# MotorControllerV_Driver1_1.net
KiCad netlist of a schematic drawn in Altium Designer
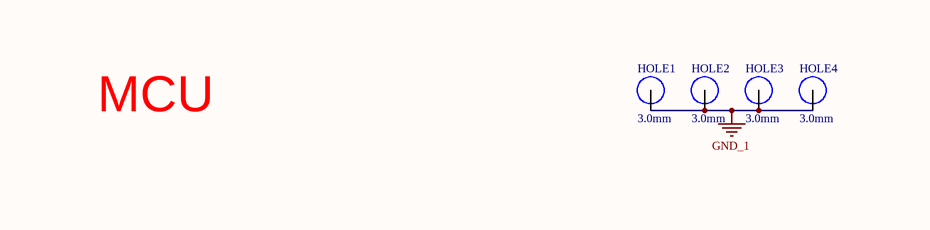
[diagram p0: MotorControllerV_Driver1.1.SchDoc, top left]
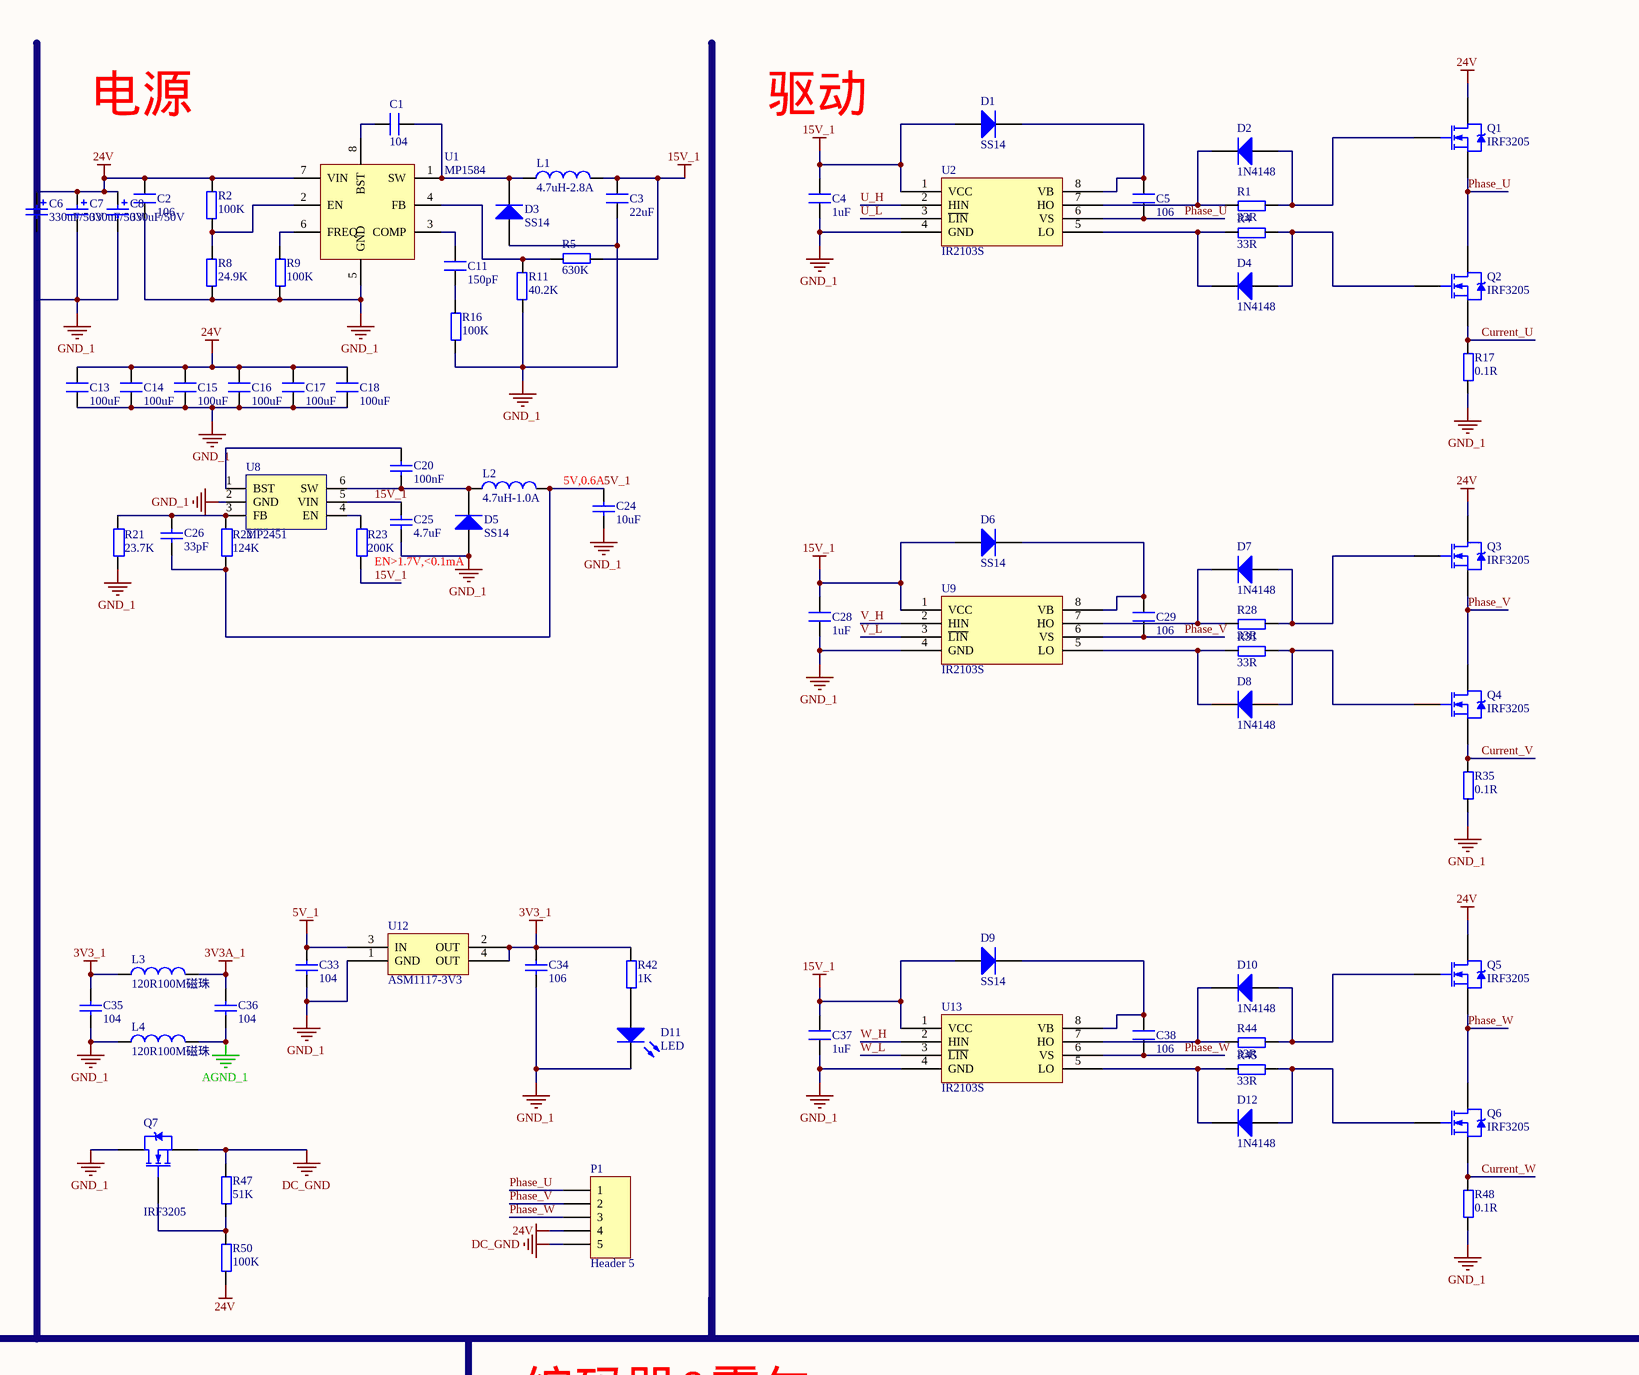
[diagram p1: MotorControllerV_Driver1.1.SchDoc, top middle]
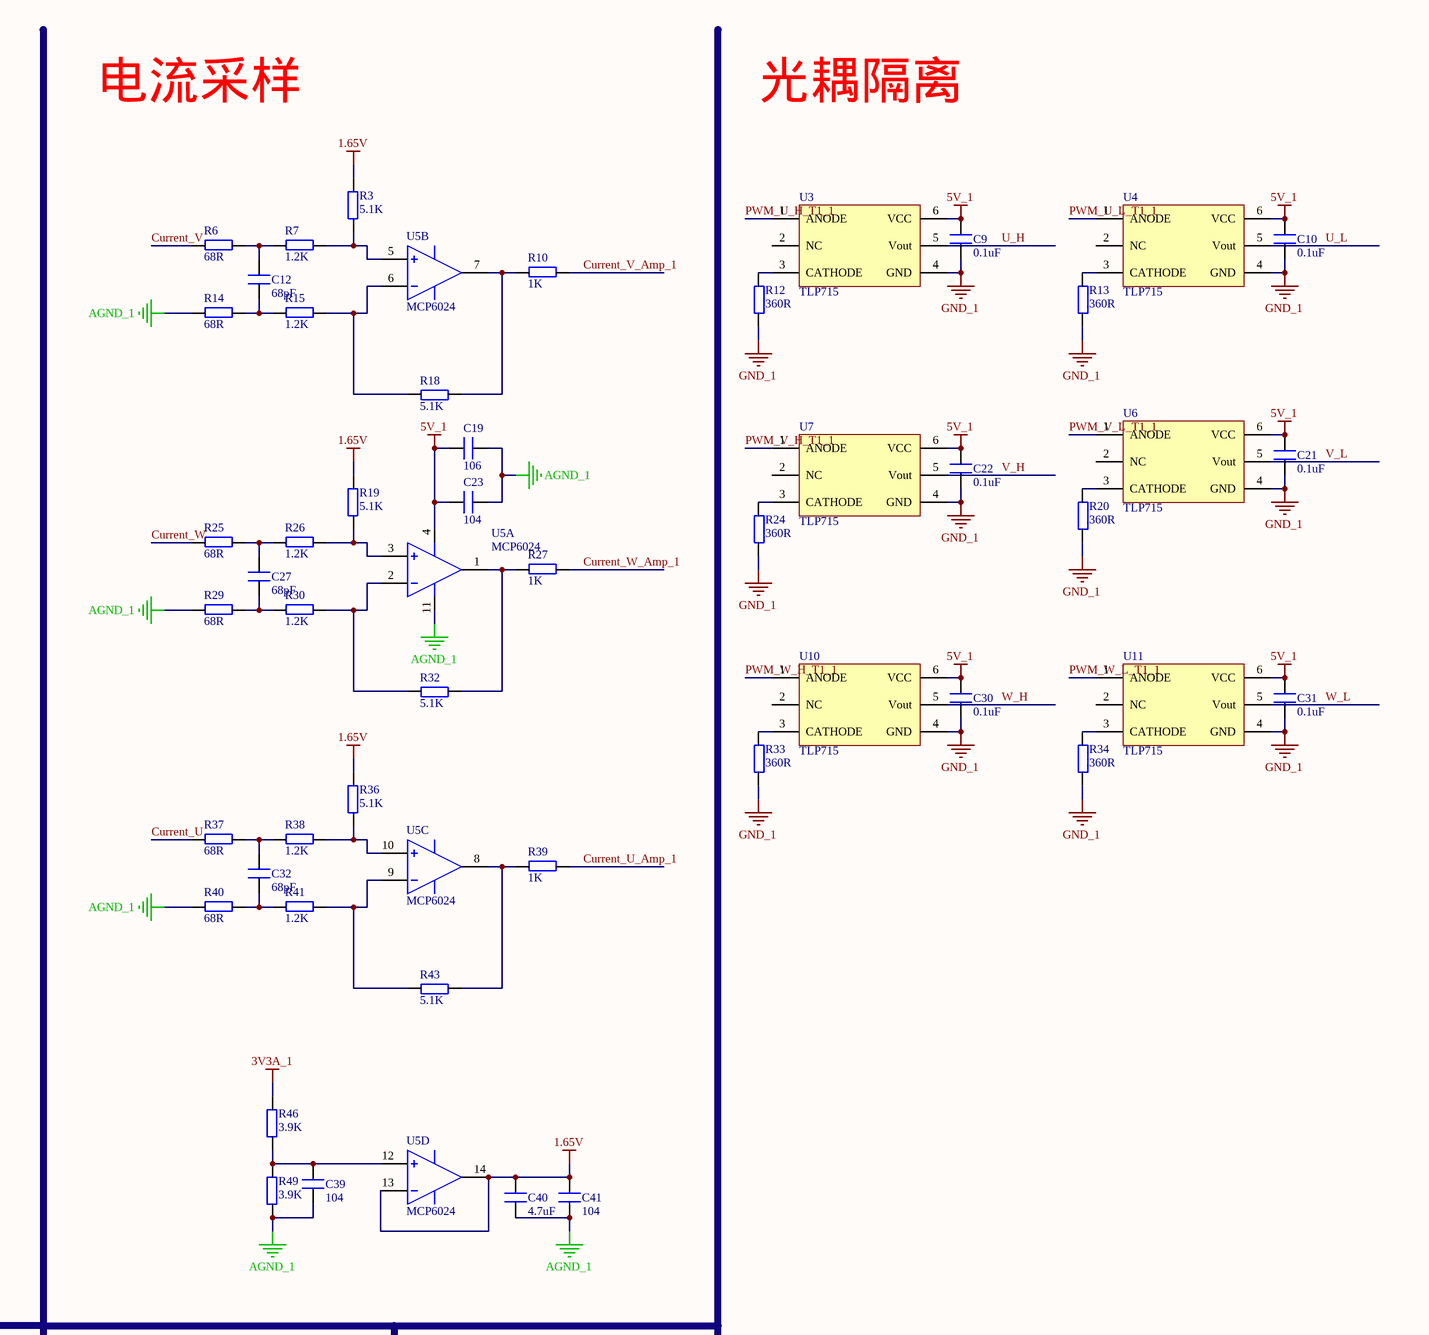
[diagram p2: MotorControllerV_Driver1.1.SchDoc, top right]
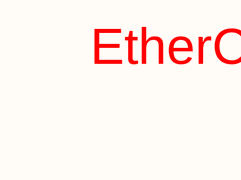
[diagram p3: MotorControllerV_Driver1.1.SchDoc, bottom left]
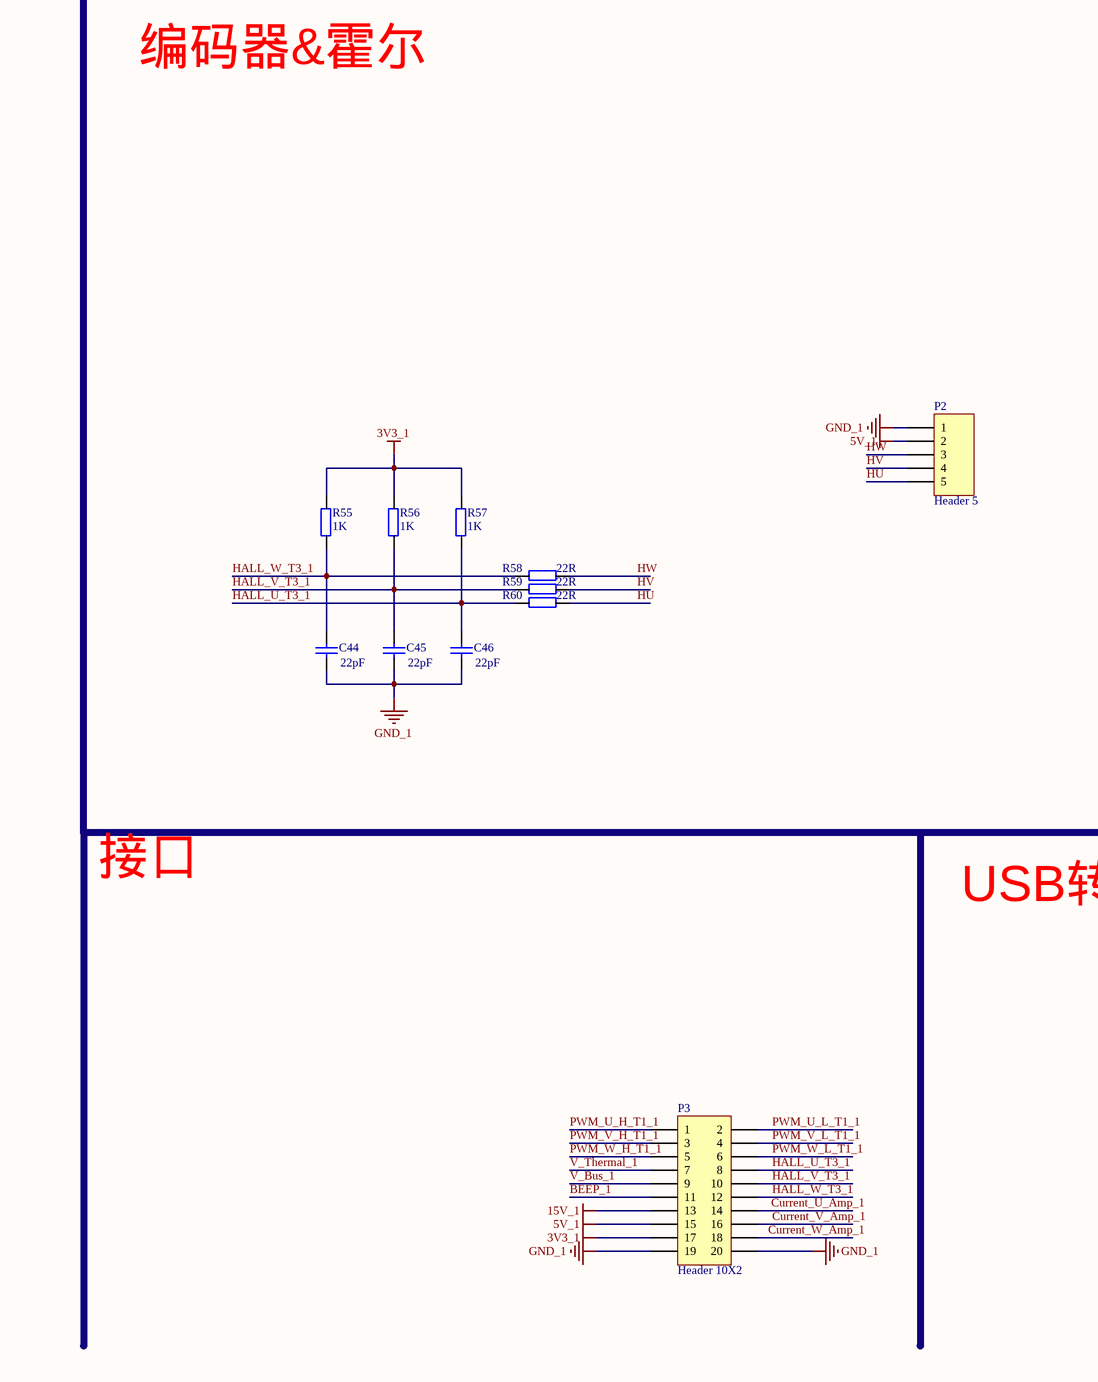
[diagram p4: MotorControllerV_Driver1.1.SchDoc, bottom middle]
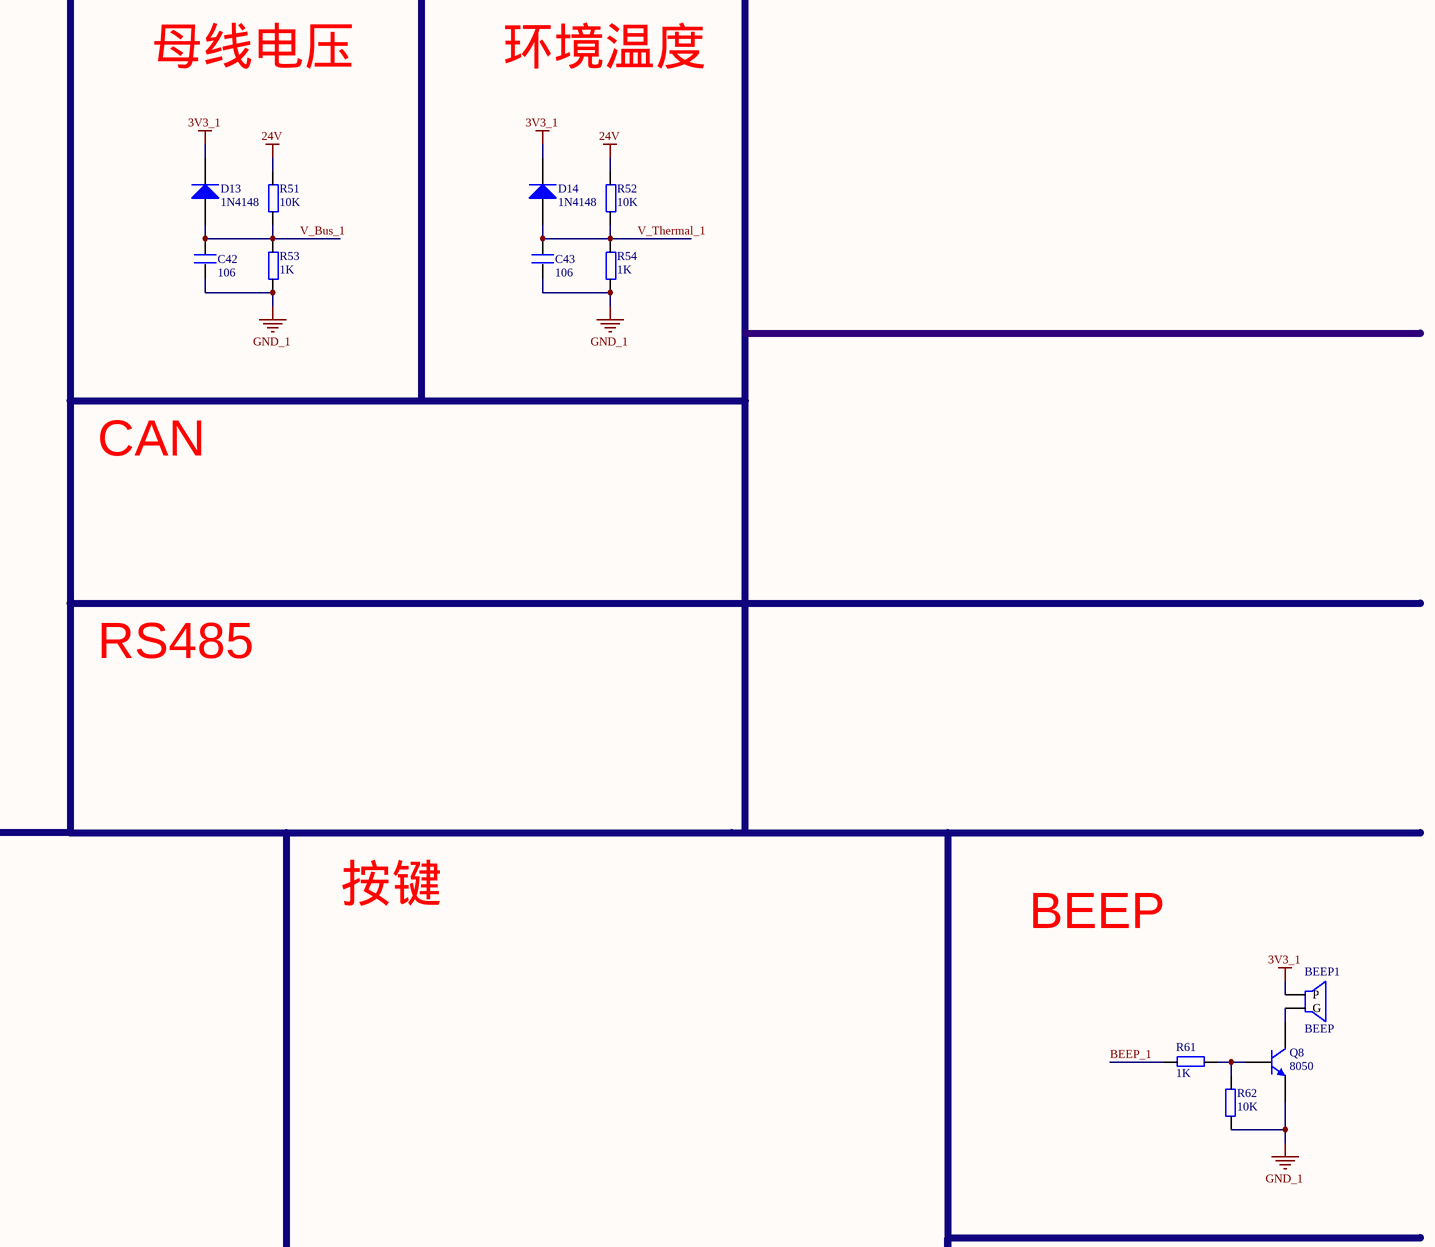
[diagram p5: MotorControllerV_Driver1.1.SchDoc, bottom right]

(export (version "E")
  (design (tool "Eeschema 10.0.6"))
  (components
    (comp (ref "BEEP1") (value "BEEP") (footprint "BEEP 5x9x5.5") (libsource (lib "MYSchlib") (part "BEEP")))
    (comp (ref "C1") (value "104") (footprint "0603_C") (libsource (lib "MYSchlib") (part "C")))
    (comp (ref "C2") (value "106") (footprint "0603_C") (libsource (lib "MYSchlib") (part "C")))
    (comp (ref "C3") (value "22uF") (footprint "0603_C") (libsource (lib "MYSchlib") (part "C")))
    (comp (ref "C4") (value "1uF") (footprint "0603_C") (libsource (lib "MYSchlib") (part "C")))
    (comp (ref "C5") (value "106") (footprint "1210_C") (libsource (lib "MYSchlib") (part "C")))
    (comp (ref "C6")
      (value "330uF/50V")
      (footprint "CM F(10*10.2)")
      (description "C+")
      (fields (field (name "PUBLISHER") "Altium Limited"))
      (libsource (lib "RLC") (part "C+"))
    )
    (comp (ref "C7")
      (value "330uF/50V")
      (footprint "CM F(10*10.2)")
      (description "C+")
      (fields (field (name "PUBLISHER") "Altium Limited"))
      (libsource (lib "RLC") (part "C+"))
    )
    (comp (ref "C8")
      (value "330uF/50V")
      (footprint "CM F(10*10.2)")
      (description "C+")
      (fields (field (name "PUBLISHER") "Altium Limited"))
      (libsource (lib "RLC") (part "C+"))
    )
    (comp (ref "C9") (value "0.1uF") (footprint "0603_C") (libsource (lib "MYSchlib") (part "C")))
    (comp (ref "C10") (value "0.1uF") (footprint "0603_C") (libsource (lib "MYSchlib") (part "C")))
    (comp (ref "C11") (value "150pF") (footprint "0603_C") (libsource (lib "MYSchlib") (part "C")))
    (comp (ref "C12") (value "68pF") (footprint "0603_C") (libsource (lib "MYSchlib") (part "C")))
    (comp (ref "C13") (value "100uF") (footprint "1210_C") (libsource (lib "MYSchlib") (part "C")))
    (comp (ref "C14") (value "100uF") (footprint "1210_C") (libsource (lib "MYSchlib") (part "C")))
    (comp (ref "C15") (value "100uF") (footprint "1210_C") (libsource (lib "MYSchlib") (part "C")))
    (comp (ref "C16") (value "100uF") (footprint "1210_C") (libsource (lib "MYSchlib") (part "C")))
    (comp (ref "C17") (value "100uF") (footprint "1210_C") (libsource (lib "MYSchlib") (part "C")))
    (comp (ref "C18") (value "100uF") (footprint "1210_C") (libsource (lib "MYSchlib") (part "C")))
    (comp (ref "C19") (value "106") (footprint "0603_C") (libsource (lib "MYSchlib") (part "C")))
    (comp (ref "C20")
      (value "100nF")
      (footprint "0603_C")
      (description "C")
      (fields (field (name "PUBLISHER") "Altium Limited"))
      (libsource (lib "RLC") (part "C"))
    )
    (comp (ref "C21") (value "0.1uF") (footprint "0603_C") (libsource (lib "MYSchlib") (part "C")))
    (comp (ref "C22") (value "0.1uF") (footprint "0603_C") (libsource (lib "MYSchlib") (part "C")))
    (comp (ref "C23") (value "104") (footprint "0603_C") (libsource (lib "MYSchlib") (part "C")))
    (comp (ref "C24")
      (value "10uF")
      (footprint "0603_C")
      (description "C")
      (fields (field (name "PUBLISHER") "Altium Limited"))
      (libsource (lib "RLC") (part "C"))
    )
    (comp (ref "C25")
      (value "4.7uF")
      (footprint "0603_C")
      (description "C")
      (fields (field (name "PUBLISHER") "Altium Limited"))
      (libsource (lib "RLC") (part "C"))
    )
    (comp (ref "C26")
      (value "33pF")
      (footprint "0603_C")
      (description "C")
      (fields (field (name "PUBLISHER") "Altium Limited"))
      (libsource (lib "RLC") (part "C"))
    )
    (comp (ref "C27") (value "68pF") (footprint "0603_C") (libsource (lib "MYSchlib") (part "C")))
    (comp (ref "C28") (value "1uF") (footprint "0603_C") (libsource (lib "MYSchlib") (part "C")))
    (comp (ref "C29") (value "106") (footprint "1210_C") (libsource (lib "MYSchlib") (part "C")))
    (comp (ref "C30") (value "0.1uF") (footprint "0603_C") (libsource (lib "MYSchlib") (part "C")))
    (comp (ref "C31") (value "0.1uF") (footprint "0603_C") (libsource (lib "MYSchlib") (part "C")))
    (comp (ref "C32") (value "68pF") (footprint "0603_C") (libsource (lib "MYSchlib") (part "C")))
    (comp (ref "C33")
      (value "104")
      (footprint "0603_C")
      (description "C")
      (fields (field (name "PUBLISHER") "Altium Limited"))
      (libsource (lib "RLC") (part "C"))
    )
    (comp (ref "C34")
      (value "106")
      (footprint "0603_C")
      (description "C")
      (fields (field (name "PUBLISHER") "Altium Limited"))
      (libsource (lib "RLC") (part "C"))
    )
    (comp (ref "C35")
      (value "104")
      (footprint "0603_C")
      (description "C")
      (fields (field (name "PUBLISHER") "Altium Limited"))
      (libsource (lib "RLC") (part "C"))
    )
    (comp (ref "C36")
      (value "104")
      (footprint "0603_C")
      (description "C")
      (fields (field (name "PUBLISHER") "Altium Limited"))
      (libsource (lib "RLC") (part "C"))
    )
    (comp (ref "C37") (value "1uF") (footprint "0603_C") (libsource (lib "MYSchlib") (part "C")))
    (comp (ref "C38") (value "106") (footprint "1210_C") (libsource (lib "MYSchlib") (part "C")))
    (comp (ref "C39") (value "104") (footprint "0603_C") (libsource (lib "MYSchlib") (part "C")))
    (comp (ref "C40") (value "4.7uF") (footprint "0603_C") (libsource (lib "MYSchlib") (part "C")))
    (comp (ref "C41") (value "104") (footprint "0603_C") (libsource (lib "MYSchlib") (part "C")))
    (comp (ref "C42") (value "106") (footprint "0603_C") (libsource (lib "MYSchlib") (part "C")))
    (comp (ref "C43") (value "106") (footprint "0603_C") (libsource (lib "MYSchlib") (part "C")))
    (comp (ref "C44")
      (value "22pF")
      (footprint "0603_C")
      (description "Capacitor")
      (fields (field (name "PUBLISHER") "Altium Limited"))
      (libsource (lib "Miscellaneous Devices") (part "Cap"))
    )
    (comp (ref "C45")
      (value "22pF")
      (footprint "0603_C")
      (description "Capacitor")
      (fields (field (name "PUBLISHER") "Altium Limited"))
      (libsource (lib "Miscellaneous Devices") (part "Cap"))
    )
    (comp (ref "C46")
      (value "22pF")
      (footprint "0603_C")
      (description "Capacitor")
      (fields (field (name "PUBLISHER") "Altium Limited"))
      (libsource (lib "Miscellaneous Devices") (part "Cap"))
    )
    (comp (ref "D1")
      (value "SS14")
      (footprint "二极管-整流桥:SOD-323")
      (description "D")
      (libsource (lib "MYSchlib") (part "Dio"))
    )
    (comp (ref "D2")
      (value "1N4148")
      (footprint "SOD-123F")
      (description "D")
      (libsource (lib "MYSchlib") (part "Dio"))
    )
    (comp (ref "D3")
      (value "SS14")
      (footprint "二极管-整流桥:SMA")
      (description "D")
      (libsource (lib "MYSchlib") (part "Dio"))
    )
    (comp (ref "D4")
      (value "1N4148")
      (footprint "SOD-123F")
      (description "D")
      (libsource (lib "MYSchlib") (part "Dio"))
    )
    (comp (ref "D5")
      (value "SS14")
      (footprint "二极管-整流桥:SOD-323")
      (description "D")
      (libsource (lib "MYSchlib") (part "Dio"))
    )
    (comp (ref "D6")
      (value "SS14")
      (footprint "二极管-整流桥:SOD-323")
      (description "D")
      (libsource (lib "MYSchlib") (part "Dio"))
    )
    (comp (ref "D7")
      (value "1N4148")
      (footprint "SOD-123F")
      (description "D")
      (libsource (lib "MYSchlib") (part "Dio"))
    )
    (comp (ref "D8")
      (value "1N4148")
      (footprint "SOD-123F")
      (description "D")
      (libsource (lib "MYSchlib") (part "Dio"))
    )
    (comp (ref "D9")
      (value "SS14")
      (footprint "二极管-整流桥:SOD-323")
      (description "D")
      (libsource (lib "MYSchlib") (part "Dio"))
    )
    (comp (ref "D10")
      (value "1N4148")
      (footprint "SOD-123F")
      (description "D")
      (libsource (lib "MYSchlib") (part "Dio"))
    )
    (comp (ref "D11") (value "LED") (footprint "0603_LED") (libsource (lib "MYSchlib") (part "LED")))
    (comp (ref "D12")
      (value "1N4148")
      (footprint "SOD-123F")
      (description "D")
      (libsource (lib "MYSchlib") (part "Dio"))
    )
    (comp (ref "D13")
      (value "1N4148")
      (footprint "SOD-123F")
      (description "D")
      (libsource (lib "MYSchlib") (part "Dio"))
    )
    (comp (ref "D14")
      (value "1N4148")
      (footprint "SOD-123F")
      (description "D")
      (libsource (lib "MYSchlib") (part "Dio"))
    )
    (comp (ref "HOLE1")
      (value "3.0mm")
      (footprint "M2.5x6+6_L")
      (fields (field (name "Comment") "HOLE"))
      (libsource (lib "MYSchlib") (part "HOLE"))
    )
    (comp (ref "HOLE2")
      (value "3.0mm")
      (footprint "M2.5x6+6_L")
      (fields (field (name "Comment") "HOLE"))
      (libsource (lib "MYSchlib") (part "HOLE"))
    )
    (comp (ref "HOLE3")
      (value "3.0mm")
      (footprint "M2.5x6+6_L")
      (fields (field (name "Comment") "HOLE"))
      (libsource (lib "MYSchlib") (part "HOLE"))
    )
    (comp (ref "HOLE4")
      (value "3.0mm")
      (footprint "M2.5x6+6_L")
      (fields (field (name "Comment") "HOLE"))
      (libsource (lib "MYSchlib") (part "HOLE"))
    )
    (comp (ref "L1")
      (value "4.7uH-2.8A")
      (footprint "CDRH74")
      (description "L")
      (fields (field (name "PUBLISHER") "Altium Limited"))
      (libsource (lib "RLC") (part "L"))
    )
    (comp (ref "L2")
      (value "4.7uH-1.0A")
      (footprint "CD32")
      (description "L")
      (fields (field (name "PUBLISHER") "Altium Limited"))
      (libsource (lib "RLC") (part "L"))
    )
    (comp (ref "L3")
      (value "120R100M磁珠")
      (footprint "0603_R")
      (description "L")
      (fields (field (name "PUBLISHER") "Altium Limited"))
      (libsource (lib "MYSchlib") (part "L_1"))
    )
    (comp (ref "L4")
      (value "120R100M磁珠")
      (footprint "0603_R")
      (description "L")
      (fields (field (name "PUBLISHER") "Altium Limited"))
      (libsource (lib "MYSchlib") (part "L_1"))
    )
    (comp (ref "P1")
      (value "Header 5")
      (footprint "HT5.08-5P")
      (description "Header, 5-Pin")
      (fields (field (name "PUBLISHER") "Altium Limited"))
      (libsource (lib "MYSchlib") (part "Header 5"))
    )
    (comp (ref "P2")
      (value "Header 5")
      (footprint "HDR2.54-WI-5P")
      (description "Header, 5-Pin")
      (fields (field (name "PUBLISHER") "Altium Limited"))
      (libsource (lib "Miscellaneous Connectors") (part "Header 5"))
    )
    (comp (ref "P3")
      (value "Header 10X2")
      (footprint "MYPcbLib:HDR2.54-LI-2x10P")
      (description "Header, 10-Pin, Dual row")
      (fields (field (name "PUBLISHER") "Altium Limited"))
      (libsource (lib "Miscellaneous Connectors") (part "Header 10X2"))
    )
    (comp (ref "Q1")
      (value "IRF3205")
      (footprint "TO252")
      (description "N-Channel Power MOSFET")
      (fields (field (name "PUBLISHER") "Altium Limited"))
      (libsource (lib "MYSchlib") (part "NMOS-2"))
    )
    (comp (ref "Q2")
      (value "IRF3205")
      (footprint "TO252")
      (description "N-Channel Power MOSFET")
      (fields (field (name "PUBLISHER") "Altium Limited"))
      (libsource (lib "MYSchlib") (part "NMOS-2"))
    )
    (comp (ref "Q3")
      (value "IRF3205")
      (footprint "TO252")
      (description "N-Channel Power MOSFET")
      (fields (field (name "PUBLISHER") "Altium Limited"))
      (libsource (lib "MYSchlib") (part "NMOS-2"))
    )
    (comp (ref "Q4")
      (value "IRF3205")
      (footprint "TO252")
      (description "N-Channel Power MOSFET")
      (fields (field (name "PUBLISHER") "Altium Limited"))
      (libsource (lib "MYSchlib") (part "NMOS-2"))
    )
    (comp (ref "Q5")
      (value "IRF3205")
      (footprint "TO252")
      (description "N-Channel Power MOSFET")
      (fields (field (name "PUBLISHER") "Altium Limited"))
      (libsource (lib "MYSchlib") (part "NMOS-2"))
    )
    (comp (ref "Q6")
      (value "IRF3205")
      (footprint "TO252")
      (description "N-Channel Power MOSFET")
      (fields (field (name "PUBLISHER") "Altium Limited"))
      (libsource (lib "MYSchlib") (part "NMOS-2"))
    )
    (comp (ref "Q7")
      (value "IRF3205")
      (footprint "TO252")
      (description "N-Channel Power MOSFET")
      (fields (field (name "PUBLISHER") "Altium Limited"))
      (libsource (lib "MYSchlib") (part "NMOS-2"))
    )
    (comp (ref "Q8")
      (value "8050")
      (footprint "SOT23")
      (description "NPN Bipolar Transistor")
      (fields (field (name "PUBLISHER") "Altium Limited"))
      (libsource (lib "MYSchlib") (part "NPN_1"))
    )
    (comp (ref "R1") (value "33R") (footprint "0603_R") (libsource (lib "MYSchlib") (part "R")))
    (comp (ref "R2") (value "100K") (footprint "0603_R") (libsource (lib "MYSchlib") (part "R")))
    (comp (ref "R3") (value "5.1K") (footprint "0603_R") (libsource (lib "MYSchlib") (part "R")))
    (comp (ref "R4") (value "33R") (footprint "0603_R") (libsource (lib "MYSchlib") (part "R")))
    (comp (ref "R5") (value "630K") (footprint "0603_R") (libsource (lib "MYSchlib") (part "R")))
    (comp (ref "R6") (value "68R") (footprint "0603_R") (libsource (lib "MYSchlib") (part "R")))
    (comp (ref "R7") (value "1.2K") (footprint "0603_R") (libsource (lib "MYSchlib") (part "R")))
    (comp (ref "R8") (value "24.9K") (footprint "0603_R") (libsource (lib "MYSchlib") (part "R")))
    (comp (ref "R9") (value "100K") (footprint "0603_R") (libsource (lib "MYSchlib") (part "R")))
    (comp (ref "R10") (value "1K") (footprint "0603_R") (libsource (lib "MYSchlib") (part "R")))
    (comp (ref "R11") (value "40.2K") (footprint "0603_R") (libsource (lib "MYSchlib") (part "R")))
    (comp (ref "R12") (value "360R") (footprint "0603_R") (libsource (lib "MYSchlib") (part "R")))
    (comp (ref "R13") (value "360R") (footprint "0603_R") (libsource (lib "MYSchlib") (part "R")))
    (comp (ref "R14") (value "68R") (footprint "0603_R") (libsource (lib "MYSchlib") (part "R")))
    (comp (ref "R15") (value "1.2K") (footprint "0603_R") (libsource (lib "MYSchlib") (part "R")))
    (comp (ref "R16") (value "100K") (footprint "0603_R") (libsource (lib "MYSchlib") (part "R")))
    (comp (ref "R17") (value "0.1R") (footprint "R_2512") (libsource (lib "MYSchlib") (part "R")))
    (comp (ref "R18") (value "5.1K") (footprint "0603_R") (libsource (lib "MYSchlib") (part "R")))
    (comp (ref "R19") (value "5.1K") (footprint "0603_R") (libsource (lib "MYSchlib") (part "R")))
    (comp (ref "R20") (value "360R") (footprint "0603_R") (libsource (lib "MYSchlib") (part "R")))
    (comp (ref "R21")
      (value "23.7K")
      (footprint "0603_R")
      (description "R")
      (fields (field (name "PUBLISHER") "Altium Limited"))
      (libsource (lib "RLC") (part "R"))
    )
    (comp (ref "R22")
      (value "124K")
      (footprint "0603_R")
      (description "R")
      (fields (field (name "PUBLISHER") "Altium Limited"))
      (libsource (lib "RLC") (part "R"))
    )
    (comp (ref "R23")
      (value "200K")
      (footprint "0603_R")
      (description "R")
      (fields (field (name "PUBLISHER") "Altium Limited"))
      (libsource (lib "RLC") (part "R"))
    )
    (comp (ref "R24") (value "360R") (footprint "0603_R") (libsource (lib "MYSchlib") (part "R")))
    (comp (ref "R25") (value "68R") (footprint "0603_R") (libsource (lib "MYSchlib") (part "R")))
    (comp (ref "R26") (value "1.2K") (footprint "0603_R") (libsource (lib "MYSchlib") (part "R")))
    (comp (ref "R27") (value "1K") (footprint "0603_R") (libsource (lib "MYSchlib") (part "R")))
    (comp (ref "R28") (value "33R") (footprint "0603_R") (libsource (lib "MYSchlib") (part "R")))
    (comp (ref "R29") (value "68R") (footprint "0603_R") (libsource (lib "MYSchlib") (part "R")))
    (comp (ref "R30") (value "1.2K") (footprint "0603_R") (libsource (lib "MYSchlib") (part "R")))
    (comp (ref "R31") (value "33R") (footprint "0603_R") (libsource (lib "MYSchlib") (part "R")))
    (comp (ref "R32") (value "5.1K") (footprint "0603_R") (libsource (lib "MYSchlib") (part "R")))
    (comp (ref "R33") (value "360R") (footprint "0603_R") (libsource (lib "MYSchlib") (part "R")))
    (comp (ref "R34") (value "360R") (footprint "0603_R") (libsource (lib "MYSchlib") (part "R")))
    (comp (ref "R35") (value "0.1R") (footprint "R_2512") (libsource (lib "MYSchlib") (part "R")))
    (comp (ref "R36") (value "5.1K") (footprint "0603_R") (libsource (lib "MYSchlib") (part "R")))
    (comp (ref "R37") (value "68R") (footprint "0603_R") (libsource (lib "MYSchlib") (part "R")))
    (comp (ref "R38") (value "1.2K") (footprint "0603_R") (libsource (lib "MYSchlib") (part "R")))
    (comp (ref "R39") (value "1K") (footprint "0603_R") (libsource (lib "MYSchlib") (part "R")))
    (comp (ref "R40") (value "68R") (footprint "0603_R") (libsource (lib "MYSchlib") (part "R")))
    (comp (ref "R41") (value "1.2K") (footprint "0603_R") (libsource (lib "MYSchlib") (part "R")))
    (comp (ref "R42") (value "1K") (footprint "0603_R") (libsource (lib "MYSchlib") (part "R")))
    (comp (ref "R43") (value "5.1K") (footprint "0603_R") (libsource (lib "MYSchlib") (part "R")))
    (comp (ref "R44") (value "33R") (footprint "0603_R") (libsource (lib "MYSchlib") (part "R")))
    (comp (ref "R45") (value "33R") (footprint "0603_R") (libsource (lib "MYSchlib") (part "R")))
    (comp (ref "R46") (value "3.9K") (footprint "0603_R") (libsource (lib "MYSchlib") (part "R")))
    (comp (ref "R47") (value "51K") (footprint "0603_R") (libsource (lib "MYSchlib") (part "R")))
    (comp (ref "R48") (value "0.1R") (footprint "R_2512") (libsource (lib "MYSchlib") (part "R")))
    (comp (ref "R49") (value "3.9K") (footprint "0603_R") (libsource (lib "MYSchlib") (part "R")))
    (comp (ref "R50") (value "100K") (footprint "0603_R") (libsource (lib "MYSchlib") (part "R")))
    (comp (ref "R51") (value "10K") (footprint "0603_R") (libsource (lib "MYSchlib") (part "R")))
    (comp (ref "R52") (value "10K") (footprint "Thermistor_MF52") (libsource (lib "MYSchlib") (part "R")))
    (comp (ref "R53") (value "1K") (footprint "0603_R") (libsource (lib "MYSchlib") (part "R")))
    (comp (ref "R54") (value "1K") (footprint "0603_R") (libsource (lib "MYSchlib") (part "R")))
    (comp (ref "R55") (value "1K") (footprint "0603_R") (libsource (lib "MYSchlib") (part "R")))
    (comp (ref "R56") (value "1K") (footprint "0603_R") (libsource (lib "MYSchlib") (part "R")))
    (comp (ref "R57") (value "1K") (footprint "0603_R") (libsource (lib "MYSchlib") (part "R")))
    (comp (ref "R58") (value "22R") (footprint "0603_R") (libsource (lib "MYSchlib") (part "R")))
    (comp (ref "R59") (value "22R") (footprint "0603_R") (libsource (lib "MYSchlib") (part "R")))
    (comp (ref "R60") (value "22R") (footprint "0603_R") (libsource (lib "MYSchlib") (part "R")))
    (comp (ref "R61") (value "1K") (footprint "0603_R") (libsource (lib "MYSchlib") (part "R")))
    (comp (ref "R62") (value "10K") (footprint "0603_R") (libsource (lib "MYSchlib") (part "R")))
    (comp (ref "U1")
      (value "MP1584")
      (footprint "MYPcbLib:SOIC-8E")
      (libsource (lib "MYSchlib") (part "MP1584"))
    )
    (comp (ref "U2") (value "IR2103S") (footprint "SOP-8") (libsource (lib "MYSchlib") (part "IR2103S")))
    (comp (ref "U3") (value "TLP715") (footprint "SOP-6") (libsource (lib "MYSchlib") (part "TLP715")))
    (comp (ref "U4") (value "TLP715") (footprint "SOP-6") (libsource (lib "MYSchlib") (part "TLP715")))
    (comp (ref "U5")
      (value "MCP6024")
      (footprint "SOIC-14_150mil")
      (libsource (lib "MYSchlib") (part "MCP6024"))
    )
    (comp (ref "U6") (value "TLP715") (footprint "SOP-6") (libsource (lib "MYSchlib") (part "TLP715")))
    (comp (ref "U7") (value "TLP715") (footprint "SOP-6") (libsource (lib "MYSchlib") (part "TLP715")))
    (comp (ref "U8") (value "MP2451") (footprint "SOT23-6") (libsource (lib "MYSchlib") (part "MP2451")))
    (comp (ref "U9") (value "IR2103S") (footprint "SOP-8") (libsource (lib "MYSchlib") (part "IR2103S")))
    (comp (ref "U10") (value "TLP715") (footprint "SOP-6") (libsource (lib "MYSchlib") (part "TLP715")))
    (comp (ref "U11") (value "TLP715") (footprint "SOP-6") (libsource (lib "MYSchlib") (part "TLP715")))
    (comp (ref "U12")
      (value "ASM1117-3V3")
      (footprint "SOT-223")
      (description "3.3V稳压芯片")
      (libsource (lib "MYSchlib") (part "ASM1117"))
    )
    (comp (ref "U13") (value "IR2103S") (footprint "SOP-8") (libsource (lib "MYSchlib") (part "IR2103S")))
  )
  (nets
    (net (code "1") (name "/BEEP_1") (class "Default")
      (node (ref "P3") (pin "11") (pinfunction "11_11") (pintype "passive"))
      (node (ref "R61") (pin "2") (pintype "passive"))
    )
    (net (code "2") (name "/Current_U") (class "Default")
      (node (ref "Q2") (pin "3") (pinfunction "S_3") (pintype "passive"))
      (node (ref "R17") (pin "2") (pintype "passive"))
      (node (ref "R37") (pin "2") (pintype "passive"))
    )
    (net (code "3") (name "/Current_U_Amp_1") (class "Default")
      (node (ref "P3") (pin "14") (pinfunction "14_14") (pintype "passive"))
      (node (ref "R39") (pin "1") (pintype "passive"))
    )
    (net (code "4") (name "/Current_V") (class "Default")
      (node (ref "Q4") (pin "3") (pinfunction "S_3") (pintype "passive"))
      (node (ref "R35") (pin "2") (pintype "passive"))
      (node (ref "R6") (pin "2") (pintype "passive"))
    )
    (net (code "5") (name "/Current_V_Amp_1") (class "Default")
      (node (ref "P3") (pin "16") (pinfunction "16_16") (pintype "passive"))
      (node (ref "R10") (pin "1") (pintype "passive"))
    )
    (net (code "6") (name "/Current_W") (class "Default")
      (node (ref "Q6") (pin "3") (pinfunction "S_3") (pintype "passive"))
      (node (ref "R25") (pin "2") (pintype "passive"))
      (node (ref "R48") (pin "2") (pintype "passive"))
    )
    (net (code "7") (name "/Current_W_Amp_1") (class "Default")
      (node (ref "P3") (pin "18") (pinfunction "18_18") (pintype "passive"))
      (node (ref "R27") (pin "1") (pintype "passive"))
    )
    (net (code "8") (name "/HALL_U_T3_1") (class "Default")
      (node (ref "C46") (pin "2") (pinfunction "2_2") (pintype "passive"))
      (node (ref "P3") (pin "8") (pinfunction "8_8") (pintype "passive"))
      (node (ref "R57") (pin "2") (pintype "passive"))
      (node (ref "R60") (pin "2") (pintype "passive"))
    )
    (net (code "9") (name "/HALL_V_T3_1") (class "Default")
      (node (ref "C45") (pin "2") (pinfunction "2_2") (pintype "passive"))
      (node (ref "P3") (pin "10") (pinfunction "10_10") (pintype "passive"))
      (node (ref "R56") (pin "2") (pintype "passive"))
      (node (ref "R59") (pin "2") (pintype "passive"))
    )
    (net (code "10") (name "/HALL_W_T3_1") (class "Default")
      (node (ref "C44") (pin "2") (pinfunction "2_2") (pintype "passive"))
      (node (ref "P3") (pin "12") (pinfunction "12_12") (pintype "passive"))
      (node (ref "R55") (pin "2") (pintype "passive"))
      (node (ref "R58") (pin "2") (pintype "passive"))
    )
    (net (code "11") (name "/HU") (class "Default")
      (node (ref "P2") (pin "5") (pinfunction "5_5") (pintype "passive"))
      (node (ref "R60") (pin "1") (pintype "passive"))
    )
    (net (code "12") (name "/HV") (class "Default")
      (node (ref "P2") (pin "4") (pinfunction "4_4") (pintype "passive"))
      (node (ref "R59") (pin "1") (pintype "passive"))
    )
    (net (code "13") (name "/HW") (class "Default")
      (node (ref "P2") (pin "3") (pinfunction "3_3") (pintype "passive"))
      (node (ref "R58") (pin "1") (pintype "passive"))
    )
    (net (code "14") (name "/PWM_U_H_T1_1") (class "Default")
      (node (ref "P3") (pin "1") (pinfunction "1_1") (pintype "passive"))
      (node (ref "U3") (pin "1") (pinfunction "ANODE_1") (pintype "passive"))
    )
    (net (code "15") (name "/PWM_U_L_T1_1") (class "Default")
      (node (ref "P3") (pin "2") (pinfunction "2_2") (pintype "passive"))
      (node (ref "U4") (pin "1") (pinfunction "ANODE_1") (pintype "passive"))
    )
    (net (code "16") (name "/PWM_V_H_T1_1") (class "Default")
      (node (ref "P3") (pin "3") (pinfunction "3_3") (pintype "passive"))
      (node (ref "U7") (pin "1") (pinfunction "ANODE_1") (pintype "passive"))
    )
    (net (code "17") (name "/PWM_V_L_T1_1") (class "Default")
      (node (ref "P3") (pin "4") (pinfunction "4_4") (pintype "passive"))
      (node (ref "U6") (pin "1") (pinfunction "ANODE_1") (pintype "passive"))
    )
    (net (code "18") (name "/PWM_W_H_T1_1") (class "Default")
      (node (ref "P3") (pin "5") (pinfunction "5_5") (pintype "passive"))
      (node (ref "U10") (pin "1") (pinfunction "ANODE_1") (pintype "passive"))
    )
    (net (code "19") (name "/PWM_W_L_T1_1") (class "Default")
      (node (ref "P3") (pin "6") (pinfunction "6_6") (pintype "passive"))
      (node (ref "U11") (pin "1") (pinfunction "ANODE_1") (pintype "passive"))
    )
    (net (code "20") (name "/Phase_U") (class "Default")
      (node (ref "C5") (pin "1") (pintype "passive"))
      (node (ref "P1") (pin "1") (pinfunction "1_1") (pintype "passive"))
      (node (ref "Q1") (pin "3") (pinfunction "S_3") (pintype "passive"))
      (node (ref "Q2") (pin "2") (pinfunction "D_2") (pintype "passive"))
      (node (ref "U2") (pin "6") (pinfunction "VS_6") (pintype "passive"))
    )
    (net (code "21") (name "/Phase_V") (class "Default")
      (node (ref "C29") (pin "1") (pintype "passive"))
      (node (ref "P1") (pin "2") (pinfunction "2_2") (pintype "passive"))
      (node (ref "Q3") (pin "3") (pinfunction "S_3") (pintype "passive"))
      (node (ref "Q4") (pin "2") (pinfunction "D_2") (pintype "passive"))
      (node (ref "U9") (pin "6") (pinfunction "VS_6") (pintype "passive"))
    )
    (net (code "22") (name "/Phase_W") (class "Default")
      (node (ref "C38") (pin "1") (pintype "passive"))
      (node (ref "P1") (pin "3") (pinfunction "3_3") (pintype "passive"))
      (node (ref "Q5") (pin "3") (pinfunction "S_3") (pintype "passive"))
      (node (ref "Q6") (pin "2") (pinfunction "D_2") (pintype "passive"))
      (node (ref "U13") (pin "6") (pinfunction "VS_6") (pintype "passive"))
    )
    (net (code "23") (name "/U_H") (class "Default")
      (node (ref "U2") (pin "2") (pinfunction "HIN_2") (pintype "passive"))
      (node (ref "U3") (pin "5") (pinfunction "Vout_5") (pintype "passive"))
    )
    (net (code "24") (name "/U_L") (class "Default")
      (node (ref "U2") (pin "3") (pinfunction "~{LIN}_3") (pintype "passive"))
      (node (ref "U4") (pin "5") (pinfunction "Vout_5") (pintype "passive"))
    )
    (net (code "25") (name "/V_Bus_1") (class "Default")
      (node (ref "C42") (pin "1") (pintype "passive"))
      (node (ref "D13") (pin "1") (pinfunction "A_1") (pintype "passive"))
      (node (ref "P3") (pin "9") (pinfunction "9_9") (pintype "passive"))
      (node (ref "R51") (pin "1") (pintype "passive"))
      (node (ref "R53") (pin "2") (pintype "passive"))
    )
    (net (code "26") (name "/V_H") (class "Default")
      (node (ref "U7") (pin "5") (pinfunction "Vout_5") (pintype "passive"))
      (node (ref "U9") (pin "2") (pinfunction "HIN_2") (pintype "passive"))
    )
    (net (code "27") (name "/V_L") (class "Default")
      (node (ref "U6") (pin "5") (pinfunction "Vout_5") (pintype "passive"))
      (node (ref "U9") (pin "3") (pinfunction "~{LIN}_3") (pintype "passive"))
    )
    (net (code "28") (name "/V_Thermal_1") (class "Default")
      (node (ref "C43") (pin "1") (pintype "passive"))
      (node (ref "D14") (pin "1") (pinfunction "A_1") (pintype "passive"))
      (node (ref "P3") (pin "7") (pinfunction "7_7") (pintype "passive"))
      (node (ref "R52") (pin "1") (pintype "passive"))
      (node (ref "R54") (pin "2") (pintype "passive"))
    )
    (net (code "29") (name "/W_H") (class "Default")
      (node (ref "U10") (pin "5") (pinfunction "Vout_5") (pintype "passive"))
      (node (ref "U13") (pin "2") (pinfunction "HIN_2") (pintype "passive"))
    )
    (net (code "30") (name "/W_L") (class "Default")
      (node (ref "U11") (pin "5") (pinfunction "Vout_5") (pintype "passive"))
      (node (ref "U13") (pin "3") (pinfunction "~{LIN}_3") (pintype "passive"))
    )
    (net (code "31") (name "1.65V") (class "Default")
      (node (ref "C40") (pin "2") (pintype "passive"))
      (node (ref "C41") (pin "2") (pintype "passive"))
      (node (ref "R19") (pin "1") (pintype "passive"))
      (node (ref "R3") (pin "1") (pintype "passive"))
      (node (ref "R36") (pin "1") (pintype "passive"))
      (node (ref "U5") (pin "13") (pinfunction "4IN-_13") (pintype "passive"))
      (node (ref "U5") (pin "14") (pinfunction "4OUT_14") (pintype "passive"))
    )
    (net (code "32") (name "3V3A_1") (class "Default")
      (node (ref "C36") (pin "2") (pinfunction "2_2") (pintype "passive"))
      (node (ref "L3") (pin "2") (pinfunction "2_2") (pintype "passive"))
      (node (ref "R46") (pin "1") (pintype "passive"))
    )
    (net (code "33") (name "3V3_1") (class "Default")
      (node (ref "BEEP1") (pin "1") (pinfunction "P_1") (pintype "passive"))
      (node (ref "C34") (pin "2") (pinfunction "2_2") (pintype "passive"))
      (node (ref "C35") (pin "2") (pinfunction "2_2") (pintype "passive"))
      (node (ref "D13") (pin "2") (pinfunction "K_2") (pintype "passive"))
      (node (ref "D14") (pin "2") (pinfunction "K_2") (pintype "passive"))
      (node (ref "L3") (pin "1") (pinfunction "1_1") (pintype "passive"))
      (node (ref "P3") (pin "17") (pinfunction "17_17") (pintype "passive"))
      (node (ref "R42") (pin "2") (pintype "passive"))
      (node (ref "R55") (pin "1") (pintype "passive"))
      (node (ref "R56") (pin "1") (pintype "passive"))
      (node (ref "R57") (pin "1") (pintype "passive"))
      (node (ref "U12") (pin "2") (pinfunction "OUT_2") (pintype "passive"))
      (node (ref "U12") (pin "4") (pinfunction "OUT_4") (pintype "passive"))
    )
    (net (code "34") (name "5V_1") (class "Default")
      (node (ref "C10") (pin "2") (pintype "passive"))
      (node (ref "C19") (pin "2") (pintype "passive"))
      (node (ref "C21") (pin "2") (pintype "passive"))
      (node (ref "C22") (pin "2") (pintype "passive"))
      (node (ref "C23") (pin "2") (pintype "passive"))
      (node (ref "C24") (pin "2") (pinfunction "2_2") (pintype "passive"))
      (node (ref "C26") (pin "2") (pinfunction "2_2") (pintype "passive"))
      (node (ref "C30") (pin "2") (pintype "passive"))
      (node (ref "C31") (pin "2") (pintype "passive"))
      (node (ref "C33") (pin "2") (pinfunction "2_2") (pintype "passive"))
      (node (ref "C9") (pin "2") (pintype "passive"))
      (node (ref "L2") (pin "2") (pinfunction "2_2") (pintype "passive"))
      (node (ref "P2") (pin "2") (pinfunction "2_2") (pintype "passive"))
      (node (ref "P3") (pin "15") (pinfunction "15_15") (pintype "passive"))
      (node (ref "R22") (pin "1") (pinfunction "1_1") (pintype "passive"))
      (node (ref "U10") (pin "6") (pinfunction "VCC_6") (pintype "passive"))
      (node (ref "U11") (pin "6") (pinfunction "VCC_6") (pintype "passive"))
      (node (ref "U12") (pin "3") (pinfunction "IN_3") (pintype "passive"))
      (node (ref "U3") (pin "6") (pinfunction "VCC_6") (pintype "passive"))
      (node (ref "U4") (pin "6") (pinfunction "VCC_6") (pintype "passive"))
      (node (ref "U5") (pin "4") (pinfunction "VCC_4") (pintype "passive"))
      (node (ref "U6") (pin "6") (pinfunction "VCC_6") (pintype "passive"))
      (node (ref "U7") (pin "6") (pinfunction "VCC_6") (pintype "passive"))
    )
    (net (code "35") (name "15V_1") (class "Default")
      (node (ref "C25") (pin "1") (pinfunction "1_1") (pintype "passive"))
      (node (ref "C28") (pin "2") (pintype "passive"))
      (node (ref "C3") (pin "1") (pintype "passive"))
      (node (ref "C37") (pin "2") (pintype "passive"))
      (node (ref "C4") (pin "2") (pintype "passive"))
      (node (ref "D1") (pin "1") (pinfunction "A_1") (pintype "passive"))
      (node (ref "D6") (pin "1") (pinfunction "A_1") (pintype "passive"))
      (node (ref "D9") (pin "1") (pinfunction "A_1") (pintype "passive"))
      (node (ref "L1") (pin "2") (pinfunction "2_2") (pintype "passive"))
      (node (ref "P3") (pin "13") (pinfunction "13_13") (pintype "passive"))
      (node (ref "R23") (pin "1") (pinfunction "1_1") (pintype "passive"))
      (node (ref "R5") (pin "1") (pintype "passive"))
      (node (ref "U13") (pin "1") (pinfunction "VCC_1") (pintype "passive"))
      (node (ref "U2") (pin "1") (pinfunction "VCC_1") (pintype "passive"))
      (node (ref "U8") (pin "5") (pinfunction "VIN_5") (pintype "passive"))
      (node (ref "U9") (pin "1") (pinfunction "VCC_1") (pintype "passive"))
    )
    (net (code "36") (name "24V") (class "Default")
      (node (ref "C13") (pin "2") (pintype "passive"))
      (node (ref "C14") (pin "2") (pintype "passive"))
      (node (ref "C15") (pin "2") (pintype "passive"))
      (node (ref "C16") (pin "2") (pintype "passive"))
      (node (ref "C17") (pin "2") (pintype "passive"))
      (node (ref "C18") (pin "2") (pintype "passive"))
      (node (ref "C2") (pin "2") (pintype "passive"))
      (node (ref "C6") (pin "1") (pinfunction "1_1") (pintype "passive"))
      (node (ref "C7") (pin "1") (pinfunction "1_1") (pintype "passive"))
      (node (ref "C8") (pin "1") (pinfunction "1_1") (pintype "passive"))
      (node (ref "P1") (pin "4") (pinfunction "4_4") (pintype "passive"))
      (node (ref "Q1") (pin "2") (pinfunction "D_2") (pintype "passive"))
      (node (ref "Q3") (pin "2") (pinfunction "D_2") (pintype "passive"))
      (node (ref "Q5") (pin "2") (pinfunction "D_2") (pintype "passive"))
      (node (ref "R2") (pin "1") (pintype "passive"))
      (node (ref "R50") (pin "1") (pintype "passive"))
      (node (ref "R51") (pin "2") (pintype "passive"))
      (node (ref "R52") (pin "2") (pintype "passive"))
      (node (ref "U1") (pin "7") (pinfunction "VIN_7") (pintype "passive"))
    )
    (net (code "37") (name "AGND_1") (class "Default")
      (node (ref "C19") (pin "1") (pintype "passive"))
      (node (ref "C23") (pin "1") (pintype "passive"))
      (node (ref "C36") (pin "1") (pinfunction "1_1") (pintype "passive"))
      (node (ref "C39") (pin "1") (pintype "passive"))
      (node (ref "C40") (pin "1") (pintype "passive"))
      (node (ref "C41") (pin "1") (pintype "passive"))
      (node (ref "L4") (pin "2") (pinfunction "2_2") (pintype "passive"))
      (node (ref "R14") (pin "2") (pintype "passive"))
      (node (ref "R29") (pin "2") (pintype "passive"))
      (node (ref "R40") (pin "2") (pintype "passive"))
      (node (ref "R49") (pin "2") (pintype "passive"))
      (node (ref "U5") (pin "11") (pinfunction "GND_11") (pintype "passive"))
    )
    (net (code "38") (name "DC_GND") (class "Default")
      (node (ref "P1") (pin "5") (pinfunction "5_5") (pintype "passive"))
      (node (ref "Q7") (pin "3") (pinfunction "S_3") (pintype "passive"))
      (node (ref "R47") (pin "2") (pintype "passive"))
    )
    (net (code "39") (name "GND_1") (class "Default")
      (node (ref "C10") (pin "1") (pintype "passive"))
      (node (ref "C13") (pin "1") (pintype "passive"))
      (node (ref "C14") (pin "1") (pintype "passive"))
      (node (ref "C15") (pin "1") (pintype "passive"))
      (node (ref "C16") (pin "1") (pintype "passive"))
      (node (ref "C17") (pin "1") (pintype "passive"))
      (node (ref "C18") (pin "1") (pintype "passive"))
      (node (ref "C2") (pin "1") (pintype "passive"))
      (node (ref "C21") (pin "1") (pintype "passive"))
      (node (ref "C22") (pin "1") (pintype "passive"))
      (node (ref "C24") (pin "1") (pinfunction "1_1") (pintype "passive"))
      (node (ref "C25") (pin "2") (pinfunction "2_2") (pintype "passive"))
      (node (ref "C28") (pin "1") (pintype "passive"))
      (node (ref "C3") (pin "2") (pintype "passive"))
      (node (ref "C30") (pin "1") (pintype "passive"))
      (node (ref "C31") (pin "1") (pintype "passive"))
      (node (ref "C33") (pin "1") (pinfunction "1_1") (pintype "passive"))
      (node (ref "C34") (pin "1") (pinfunction "1_1") (pintype "passive"))
      (node (ref "C35") (pin "1") (pinfunction "1_1") (pintype "passive"))
      (node (ref "C37") (pin "1") (pintype "passive"))
      (node (ref "C4") (pin "1") (pintype "passive"))
      (node (ref "C42") (pin "2") (pintype "passive"))
      (node (ref "C43") (pin "2") (pintype "passive"))
      (node (ref "C44") (pin "1") (pinfunction "1_1") (pintype "passive"))
      (node (ref "C45") (pin "1") (pinfunction "1_1") (pintype "passive"))
      (node (ref "C46") (pin "1") (pinfunction "1_1") (pintype "passive"))
      (node (ref "C6") (pin "2") (pinfunction "2_2") (pintype "passive"))
      (node (ref "C7") (pin "2") (pinfunction "2_2") (pintype "passive"))
      (node (ref "C8") (pin "2") (pinfunction "2_2") (pintype "passive"))
      (node (ref "C9") (pin "1") (pintype "passive"))
      (node (ref "D11") (pin "2") (pinfunction "K_2") (pintype "passive"))
      (node (ref "D3") (pin "1") (pinfunction "A_1") (pintype "passive"))
      (node (ref "D5") (pin "1") (pinfunction "A_1") (pintype "passive"))
      (node (ref "HOLE1") (pin "1") (pintype "passive"))
      (node (ref "HOLE2") (pin "1") (pintype "passive"))
      (node (ref "HOLE3") (pin "1") (pintype "passive"))
      (node (ref "HOLE4") (pin "1") (pintype "passive"))
      (node (ref "L4") (pin "1") (pinfunction "1_1") (pintype "passive"))
      (node (ref "P2") (pin "1") (pinfunction "1_1") (pintype "passive"))
      (node (ref "P3") (pin "19") (pinfunction "19_19") (pintype "passive"))
      (node (ref "P3") (pin "20") (pinfunction "20_20") (pintype "passive"))
      (node (ref "Q7") (pin "2") (pinfunction "D_2") (pintype "passive"))
      (node (ref "Q8") (pin "2") (pinfunction "E_2") (pintype "passive"))
      (node (ref "R11") (pin "2") (pintype "passive"))
      (node (ref "R12") (pin "1") (pintype "passive"))
      (node (ref "R13") (pin "1") (pintype "passive"))
      (node (ref "R16") (pin "1") (pintype "passive"))
      (node (ref "R17") (pin "1") (pintype "passive"))
      (node (ref "R20") (pin "1") (pintype "passive"))
      (node (ref "R21") (pin "1") (pinfunction "1_1") (pintype "passive"))
      (node (ref "R24") (pin "1") (pintype "passive"))
      (node (ref "R33") (pin "1") (pintype "passive"))
      (node (ref "R34") (pin "1") (pintype "passive"))
      (node (ref "R35") (pin "1") (pintype "passive"))
      (node (ref "R48") (pin "1") (pintype "passive"))
      (node (ref "R53") (pin "1") (pintype "passive"))
      (node (ref "R54") (pin "1") (pintype "passive"))
      (node (ref "R62") (pin "2") (pintype "passive"))
      (node (ref "R8") (pin "2") (pintype "passive"))
      (node (ref "R9") (pin "1") (pintype "passive"))
      (node (ref "U1") (pin "5") (pinfunction "GND_5") (pintype "passive"))
      (node (ref "U10") (pin "4") (pinfunction "GND_4") (pintype "passive"))
      (node (ref "U11") (pin "4") (pinfunction "GND_4") (pintype "passive"))
      (node (ref "U12") (pin "1") (pinfunction "GND_1") (pintype "passive"))
      (node (ref "U13") (pin "4") (pinfunction "GND_4") (pintype "passive"))
      (node (ref "U2") (pin "4") (pinfunction "GND_4") (pintype "passive"))
      (node (ref "U3") (pin "4") (pinfunction "GND_4") (pintype "passive"))
      (node (ref "U4") (pin "4") (pinfunction "GND_4") (pintype "passive"))
      (node (ref "U6") (pin "4") (pinfunction "GND_4") (pintype "passive"))
      (node (ref "U7") (pin "4") (pinfunction "GND_4") (pintype "passive"))
      (node (ref "U8") (pin "2") (pinfunction "GND_2") (pintype "passive"))
      (node (ref "U9") (pin "4") (pinfunction "GND_4") (pintype "passive"))
    )
    (net (code "40") (name "Net-(BEEP1-G)") (class "Default")
      (node (ref "BEEP1") (pin "2") (pinfunction "G_2") (pintype "passive"))
      (node (ref "Q8") (pin "3") (pinfunction "C_3") (pintype "passive"))
    )
    (net (code "41") (name "Net-(C11-Pad2)") (class "Default")
      (node (ref "C11") (pin "2") (pintype "passive"))
      (node (ref "R16") (pin "2") (pintype "passive"))
    )
    (net (code "42") (name "Net-(C12-Pad1)") (class "Default")
      (node (ref "C12") (pin "1") (pintype "passive"))
      (node (ref "R14") (pin "1") (pintype "passive"))
      (node (ref "R15") (pin "2") (pintype "passive"))
    )
    (net (code "43") (name "Net-(C12-Pad2)") (class "Default")
      (node (ref "C12") (pin "2") (pintype "passive"))
      (node (ref "R6") (pin "1") (pintype "passive"))
      (node (ref "R7") (pin "2") (pintype "passive"))
    )
    (net (code "44") (name "Net-(C27-Pad1)") (class "Default")
      (node (ref "C27") (pin "1") (pintype "passive"))
      (node (ref "R29") (pin "1") (pintype "passive"))
      (node (ref "R30") (pin "2") (pintype "passive"))
    )
    (net (code "45") (name "Net-(C27-Pad2)") (class "Default")
      (node (ref "C27") (pin "2") (pintype "passive"))
      (node (ref "R25") (pin "1") (pintype "passive"))
      (node (ref "R26") (pin "2") (pintype "passive"))
    )
    (net (code "46") (name "Net-(C32-Pad1)") (class "Default")
      (node (ref "C32") (pin "1") (pintype "passive"))
      (node (ref "R40") (pin "1") (pintype "passive"))
      (node (ref "R41") (pin "2") (pintype "passive"))
    )
    (net (code "47") (name "Net-(C32-Pad2)") (class "Default")
      (node (ref "C32") (pin "2") (pintype "passive"))
      (node (ref "R37") (pin "1") (pintype "passive"))
      (node (ref "R38") (pin "2") (pintype "passive"))
    )
    (net (code "48") (name "Net-(D1-K)") (class "Default")
      (node (ref "C5") (pin "2") (pintype "passive"))
      (node (ref "D1") (pin "2") (pinfunction "K_2") (pintype "passive"))
      (node (ref "U2") (pin "8") (pinfunction "VB_8") (pintype "passive"))
    )
    (net (code "49") (name "Net-(D2-A)") (class "Default")
      (node (ref "D2") (pin "1") (pinfunction "A_1") (pintype "passive"))
      (node (ref "Q1") (pin "1") (pinfunction "G_1") (pintype "passive"))
      (node (ref "R1") (pin "2") (pintype "passive"))
    )
    (net (code "50") (name "Net-(D2-K)") (class "Default")
      (node (ref "D2") (pin "2") (pinfunction "K_2") (pintype "passive"))
      (node (ref "R1") (pin "1") (pintype "passive"))
      (node (ref "U2") (pin "7") (pinfunction "HO_7") (pintype "passive"))
    )
    (net (code "51") (name "Net-(D3-K)") (class "Default")
      (node (ref "C1") (pin "1") (pintype "passive"))
      (node (ref "D3") (pin "2") (pinfunction "K_2") (pintype "passive"))
      (node (ref "L1") (pin "1") (pinfunction "1_1") (pintype "passive"))
      (node (ref "U1") (pin "1") (pinfunction "SW_1") (pintype "passive"))
    )
    (net (code "52") (name "Net-(D4-A)") (class "Default")
      (node (ref "D4") (pin "1") (pinfunction "A_1") (pintype "passive"))
      (node (ref "Q2") (pin "1") (pinfunction "G_1") (pintype "passive"))
      (node (ref "R4") (pin "2") (pintype "passive"))
    )
    (net (code "53") (name "Net-(D4-K)") (class "Default")
      (node (ref "D4") (pin "2") (pinfunction "K_2") (pintype "passive"))
      (node (ref "R4") (pin "1") (pintype "passive"))
      (node (ref "U2") (pin "5") (pinfunction "LO_5") (pintype "passive"))
    )
    (net (code "54") (name "Net-(D5-K)") (class "Default")
      (node (ref "C20") (pin "1") (pinfunction "1_1") (pintype "passive"))
      (node (ref "D5") (pin "2") (pinfunction "K_2") (pintype "passive"))
      (node (ref "L2") (pin "1") (pinfunction "1_1") (pintype "passive"))
      (node (ref "U8") (pin "6") (pinfunction "SW_6") (pintype "passive"))
    )
    (net (code "55") (name "Net-(D6-K)") (class "Default")
      (node (ref "C29") (pin "2") (pintype "passive"))
      (node (ref "D6") (pin "2") (pinfunction "K_2") (pintype "passive"))
      (node (ref "U9") (pin "8") (pinfunction "VB_8") (pintype "passive"))
    )
    (net (code "56") (name "Net-(D7-A)") (class "Default")
      (node (ref "D7") (pin "1") (pinfunction "A_1") (pintype "passive"))
      (node (ref "Q3") (pin "1") (pinfunction "G_1") (pintype "passive"))
      (node (ref "R28") (pin "2") (pintype "passive"))
    )
    (net (code "57") (name "Net-(D7-K)") (class "Default")
      (node (ref "D7") (pin "2") (pinfunction "K_2") (pintype "passive"))
      (node (ref "R28") (pin "1") (pintype "passive"))
      (node (ref "U9") (pin "7") (pinfunction "HO_7") (pintype "passive"))
    )
    (net (code "58") (name "Net-(D8-A)") (class "Default")
      (node (ref "D8") (pin "1") (pinfunction "A_1") (pintype "passive"))
      (node (ref "Q4") (pin "1") (pinfunction "G_1") (pintype "passive"))
      (node (ref "R31") (pin "2") (pintype "passive"))
    )
    (net (code "59") (name "Net-(D8-K)") (class "Default")
      (node (ref "D8") (pin "2") (pinfunction "K_2") (pintype "passive"))
      (node (ref "R31") (pin "1") (pintype "passive"))
      (node (ref "U9") (pin "5") (pinfunction "LO_5") (pintype "passive"))
    )
    (net (code "60") (name "Net-(D9-K)") (class "Default")
      (node (ref "C38") (pin "2") (pintype "passive"))
      (node (ref "D9") (pin "2") (pinfunction "K_2") (pintype "passive"))
      (node (ref "U13") (pin "8") (pinfunction "VB_8") (pintype "passive"))
    )
    (net (code "61") (name "Net-(D10-A)") (class "Default")
      (node (ref "D10") (pin "1") (pinfunction "A_1") (pintype "passive"))
      (node (ref "Q5") (pin "1") (pinfunction "G_1") (pintype "passive"))
      (node (ref "R44") (pin "2") (pintype "passive"))
    )
    (net (code "62") (name "Net-(D10-K)") (class "Default")
      (node (ref "D10") (pin "2") (pinfunction "K_2") (pintype "passive"))
      (node (ref "R44") (pin "1") (pintype "passive"))
      (node (ref "U13") (pin "7") (pinfunction "HO_7") (pintype "passive"))
    )
    (net (code "63") (name "Net-(D11-A)") (class "Default")
      (node (ref "D11") (pin "1") (pinfunction "A_1") (pintype "passive"))
      (node (ref "R42") (pin "1") (pintype "passive"))
    )
    (net (code "64") (name "Net-(D12-A)") (class "Default")
      (node (ref "D12") (pin "1") (pinfunction "A_1") (pintype "passive"))
      (node (ref "Q6") (pin "1") (pinfunction "G_1") (pintype "passive"))
      (node (ref "R45") (pin "2") (pintype "passive"))
    )
    (net (code "65") (name "Net-(D12-K)") (class "Default")
      (node (ref "D12") (pin "2") (pinfunction "K_2") (pintype "passive"))
      (node (ref "R45") (pin "1") (pintype "passive"))
      (node (ref "U13") (pin "5") (pinfunction "LO_5") (pintype "passive"))
    )
    (net (code "66") (name "Net-(Q7-G)") (class "Default")
      (node (ref "Q7") (pin "1") (pinfunction "G_1") (pintype "passive"))
      (node (ref "R47") (pin "1") (pintype "passive"))
      (node (ref "R50") (pin "2") (pintype "passive"))
    )
    (net (code "67") (name "Net-(Q8-B)") (class "Default")
      (node (ref "Q8") (pin "1") (pinfunction "B_1") (pintype "passive"))
      (node (ref "R61") (pin "1") (pintype "passive"))
      (node (ref "R62") (pin "1") (pintype "passive"))
    )
    (net (code "68") (name "Net-(U1-BST)") (class "Default")
      (node (ref "C1") (pin "2") (pintype "passive"))
      (node (ref "U1") (pin "8") (pinfunction "BST_8") (pintype "passive"))
    )
    (net (code "69") (name "Net-(U1-COMP)") (class "Default")
      (node (ref "C11") (pin "1") (pintype "passive"))
      (node (ref "U1") (pin "3") (pinfunction "COMP_3") (pintype "passive"))
    )
    (net (code "70") (name "Net-(U1-EN)") (class "Default")
      (node (ref "R2") (pin "2") (pintype "passive"))
      (node (ref "R8") (pin "1") (pintype "passive"))
      (node (ref "U1") (pin "2") (pinfunction "EN_2") (pintype "passive"))
    )
    (net (code "71") (name "Net-(U1-FB)") (class "Default")
      (node (ref "R11") (pin "1") (pintype "passive"))
      (node (ref "R5") (pin "2") (pintype "passive"))
      (node (ref "U1") (pin "4") (pinfunction "FB_4") (pintype "passive"))
    )
    (net (code "72") (name "Net-(U1-FREQ)") (class "Default")
      (node (ref "R9") (pin "2") (pintype "passive"))
      (node (ref "U1") (pin "6") (pinfunction "FREQ_6") (pintype "passive"))
    )
    (net (code "73") (name "Net-(U3-CATHODE)") (class "Default")
      (node (ref "R12") (pin "2") (pintype "passive"))
      (node (ref "U3") (pin "3") (pinfunction "CATHODE_3") (pintype "passive"))
    )
    (net (code "74") (name "Net-(U4-CATHODE)") (class "Default")
      (node (ref "R13") (pin "2") (pintype "passive"))
      (node (ref "U4") (pin "3") (pinfunction "CATHODE_3") (pintype "passive"))
    )
    (net (code "75") (name "Net-(U5A-1IN+)") (class "Default")
      (node (ref "R19") (pin "2") (pintype "passive"))
      (node (ref "R26") (pin "1") (pintype "passive"))
      (node (ref "U5") (pin "3") (pinfunction "1IN+_3") (pintype "passive"))
    )
    (net (code "76") (name "Net-(U5A-1IN-)") (class "Default")
      (node (ref "R30") (pin "1") (pintype "passive"))
      (node (ref "R32") (pin "1") (pintype "passive"))
      (node (ref "U5") (pin "2") (pinfunction "1IN-_2") (pintype "passive"))
    )
    (net (code "77") (name "Net-(U5A-1OUT)") (class "Default")
      (node (ref "R27") (pin "2") (pintype "passive"))
      (node (ref "R32") (pin "2") (pintype "passive"))
      (node (ref "U5") (pin "1") (pinfunction "1OUT_1") (pintype "passive"))
    )
    (net (code "78") (name "Net-(U5B-2IN+)") (class "Default")
      (node (ref "R3") (pin "2") (pintype "passive"))
      (node (ref "R7") (pin "1") (pintype "passive"))
      (node (ref "U5") (pin "5") (pinfunction "2IN+_5") (pintype "passive"))
    )
    (net (code "79") (name "Net-(U5B-2IN-)") (class "Default")
      (node (ref "R15") (pin "1") (pintype "passive"))
      (node (ref "R18") (pin "1") (pintype "passive"))
      (node (ref "U5") (pin "6") (pinfunction "2IN-_6") (pintype "passive"))
    )
    (net (code "80") (name "Net-(U5B-2OUT)") (class "Default")
      (node (ref "R10") (pin "2") (pintype "passive"))
      (node (ref "R18") (pin "2") (pintype "passive"))
      (node (ref "U5") (pin "7") (pinfunction "2OUT_7") (pintype "passive"))
    )
    (net (code "81") (name "Net-(U5C-3IN+)") (class "Default")
      (node (ref "R36") (pin "2") (pintype "passive"))
      (node (ref "R38") (pin "1") (pintype "passive"))
      (node (ref "U5") (pin "10") (pinfunction "3IN+_10") (pintype "passive"))
    )
    (net (code "82") (name "Net-(U5C-3IN-)") (class "Default")
      (node (ref "R41") (pin "1") (pintype "passive"))
      (node (ref "R43") (pin "1") (pintype "passive"))
      (node (ref "U5") (pin "9") (pinfunction "3IN-_9") (pintype "passive"))
    )
    (net (code "83") (name "Net-(U5C-3OUT)") (class "Default")
      (node (ref "R39") (pin "2") (pintype "passive"))
      (node (ref "R43") (pin "2") (pintype "passive"))
      (node (ref "U5") (pin "8") (pinfunction "3OUT_8") (pintype "passive"))
    )
    (net (code "84") (name "Net-(U5D-4IN+)") (class "Default")
      (node (ref "C39") (pin "2") (pintype "passive"))
      (node (ref "R46") (pin "2") (pintype "passive"))
      (node (ref "R49") (pin "1") (pintype "passive"))
      (node (ref "U5") (pin "12") (pinfunction "4IN+_12") (pintype "passive"))
    )
    (net (code "85") (name "Net-(U6-CATHODE)") (class "Default")
      (node (ref "R20") (pin "2") (pintype "passive"))
      (node (ref "U6") (pin "3") (pinfunction "CATHODE_3") (pintype "passive"))
    )
    (net (code "86") (name "Net-(U7-CATHODE)") (class "Default")
      (node (ref "R24") (pin "2") (pintype "passive"))
      (node (ref "U7") (pin "3") (pinfunction "CATHODE_3") (pintype "passive"))
    )
    (net (code "87") (name "Net-(U8-BST)") (class "Default")
      (node (ref "C20") (pin "2") (pinfunction "2_2") (pintype "passive"))
      (node (ref "U8") (pin "1") (pinfunction "BST_1") (pintype "passive"))
    )
    (net (code "88") (name "Net-(U8-EN)") (class "Default")
      (node (ref "R23") (pin "2") (pinfunction "2_2") (pintype "passive"))
      (node (ref "U8") (pin "4") (pinfunction "EN_4") (pintype "passive"))
    )
    (net (code "89") (name "Net-(U8-FB)") (class "Default")
      (node (ref "C26") (pin "1") (pinfunction "1_1") (pintype "passive"))
      (node (ref "R21") (pin "2") (pinfunction "2_2") (pintype "passive"))
      (node (ref "R22") (pin "2") (pinfunction "2_2") (pintype "passive"))
      (node (ref "U8") (pin "3") (pinfunction "FB_3") (pintype "passive"))
    )
    (net (code "90") (name "Net-(U10-CATHODE)") (class "Default")
      (node (ref "R33") (pin "2") (pintype "passive"))
      (node (ref "U10") (pin "3") (pinfunction "CATHODE_3") (pintype "passive"))
    )
    (net (code "91") (name "Net-(U11-CATHODE)") (class "Default")
      (node (ref "R34") (pin "2") (pintype "passive"))
      (node (ref "U11") (pin "3") (pinfunction "CATHODE_3") (pintype "passive"))
    )
    (net (code "92") (name "unconnected-(U3-NC-Pad2)") (class "Default")
      (node (ref "U3") (pin "2") (pinfunction "NC_2") (pintype "passive"))
    )
    (net (code "93") (name "unconnected-(U4-NC-Pad2)") (class "Default")
      (node (ref "U4") (pin "2") (pinfunction "NC_2") (pintype "passive"))
    )
    (net (code "94") (name "unconnected-(U6-NC-Pad2)") (class "Default")
      (node (ref "U6") (pin "2") (pinfunction "NC_2") (pintype "passive"))
    )
    (net (code "95") (name "unconnected-(U7-NC-Pad2)") (class "Default")
      (node (ref "U7") (pin "2") (pinfunction "NC_2") (pintype "passive"))
    )
    (net (code "96") (name "unconnected-(U10-NC-Pad2)") (class "Default")
      (node (ref "U10") (pin "2") (pinfunction "NC_2") (pintype "passive"))
    )
    (net (code "97") (name "unconnected-(U11-NC-Pad2)") (class "Default")
      (node (ref "U11") (pin "2") (pinfunction "NC_2") (pintype "passive"))
    )
  )
)
